# 74HC595_Sch.net
KiCad netlist of a schematic drawn in Altium Designer
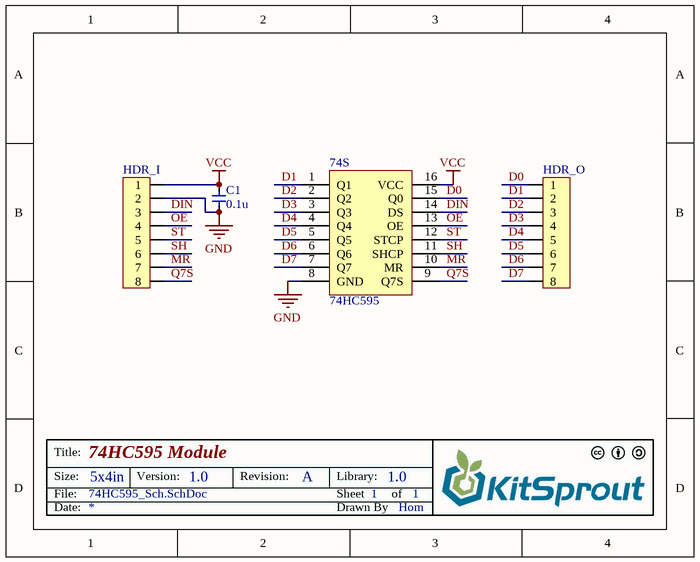
[diagram p0: 74HC595_Sch.SchDoc]

(export (version "E")
  (design (tool "Eeschema 10.0.6"))
  (components
    (comp (ref "74S")
      (value "74HC595")
      (footprint "PCB_IntegratedCircuit:SOIC_E150_16")
      (description "74 Series")
      (libsource (lib "SCH_IntegratedCircuit") (part "74HC595"))
    )
    (comp (ref "C1")
      (value "0.1u")
      (footprint "PCB_PassiveCap:CAP_0603")
      (description "Capacitor")
      (fields (field (name "Comment") "Cap_0603"))
      (libsource (lib "SCH_Passive") (part "Cap_0603"))
    )
    (comp (ref "HDR_I")
      (value "HDR1x8_2.54")
      (footprint "PCB_ConnectorHDR:HDR1X8_2.54_180")
      (description "Header")
      (libsource (lib "SCH_ConnectorHDR") (part "HDR1x8_2.54T"))
    )
    (comp (ref "HDR_O")
      (value "HDR1x8_2.54")
      (footprint "PCB_ConnectorHDR:HDR1X8_2.54_180")
      (description "Header")
      (libsource (lib "SCH_ConnectorHDR") (part "HDR1x8_2.54"))
    )
  )
  (nets
    (net (code "1") (name "/D0") (class "Default")
      (node (ref "74S") (pin "15") (pinfunction "Q0_15") (pintype "passive"))
      (node (ref "HDR_O") (pin "1") (pinfunction "1_1") (pintype "passive"))
    )
    (net (code "2") (name "/D1") (class "Default")
      (node (ref "74S") (pin "1") (pinfunction "Q1_1") (pintype "passive"))
      (node (ref "HDR_O") (pin "2") (pinfunction "2_2") (pintype "passive"))
    )
    (net (code "3") (name "/D2") (class "Default")
      (node (ref "74S") (pin "2") (pinfunction "Q2_2") (pintype "passive"))
      (node (ref "HDR_O") (pin "3") (pinfunction "3_3") (pintype "passive"))
    )
    (net (code "4") (name "/D3") (class "Default")
      (node (ref "74S") (pin "3") (pinfunction "Q3_3") (pintype "passive"))
      (node (ref "HDR_O") (pin "4") (pinfunction "4_4") (pintype "passive"))
    )
    (net (code "5") (name "/D4") (class "Default")
      (node (ref "74S") (pin "4") (pinfunction "Q4_4") (pintype "passive"))
      (node (ref "HDR_O") (pin "5") (pinfunction "5_5") (pintype "passive"))
    )
    (net (code "6") (name "/D5") (class "Default")
      (node (ref "74S") (pin "5") (pinfunction "Q5_5") (pintype "passive"))
      (node (ref "HDR_O") (pin "6") (pinfunction "6_6") (pintype "passive"))
    )
    (net (code "7") (name "/D6") (class "Default")
      (node (ref "74S") (pin "6") (pinfunction "Q6_6") (pintype "passive"))
      (node (ref "HDR_O") (pin "7") (pinfunction "7_7") (pintype "passive"))
    )
    (net (code "8") (name "/D7") (class "Default")
      (node (ref "74S") (pin "7") (pinfunction "Q7_7") (pintype "passive"))
      (node (ref "HDR_O") (pin "8") (pinfunction "8_8") (pintype "passive"))
    )
    (net (code "9") (name "/DIN") (class "Default")
      (node (ref "74S") (pin "14") (pinfunction "DS_14") (pintype "passive"))
      (node (ref "HDR_I") (pin "3") (pinfunction "3_3") (pintype "passive"))
    )
    (net (code "10") (name "/MR") (class "Default")
      (node (ref "74S") (pin "10") (pinfunction "MR_10") (pintype "passive"))
      (node (ref "HDR_I") (pin "7") (pinfunction "7_7") (pintype "passive"))
    )
    (net (code "11") (name "/OE") (class "Default")
      (node (ref "74S") (pin "13") (pinfunction "OE_13") (pintype "passive"))
      (node (ref "HDR_I") (pin "4") (pinfunction "4_4") (pintype "passive"))
    )
    (net (code "12") (name "/Q7S") (class "Default")
      (node (ref "74S") (pin "9") (pinfunction "Q7S_9") (pintype "passive"))
      (node (ref "HDR_I") (pin "8") (pinfunction "8_8") (pintype "passive"))
    )
    (net (code "13") (name "/SH") (class "Default")
      (node (ref "74S") (pin "11") (pinfunction "SHCP_11") (pintype "passive"))
      (node (ref "HDR_I") (pin "6") (pinfunction "6_6") (pintype "passive"))
    )
    (net (code "14") (name "/ST") (class "Default")
      (node (ref "74S") (pin "12") (pinfunction "STCP_12") (pintype "passive"))
      (node (ref "HDR_I") (pin "5") (pinfunction "5_5") (pintype "passive"))
    )
    (net (code "15") (name "GND") (class "Default")
      (node (ref "74S") (pin "8") (pinfunction "GND_8") (pintype "passive"))
      (node (ref "C1") (pin "1") (pinfunction "1_1") (pintype "passive"))
      (node (ref "HDR_I") (pin "2") (pinfunction "2_2") (pintype "passive"))
    )
    (net (code "16") (name "VCC") (class "Default")
      (node (ref "74S") (pin "16") (pinfunction "VCC_16") (pintype "passive"))
      (node (ref "C1") (pin "2") (pinfunction "2_2") (pintype "passive"))
      (node (ref "HDR_I") (pin "1") (pinfunction "1_1") (pintype "passive"))
    )
  )
)
